# PCB-SSB-1x4.net
KiCad netlist of a schematic drawn in EAGLE
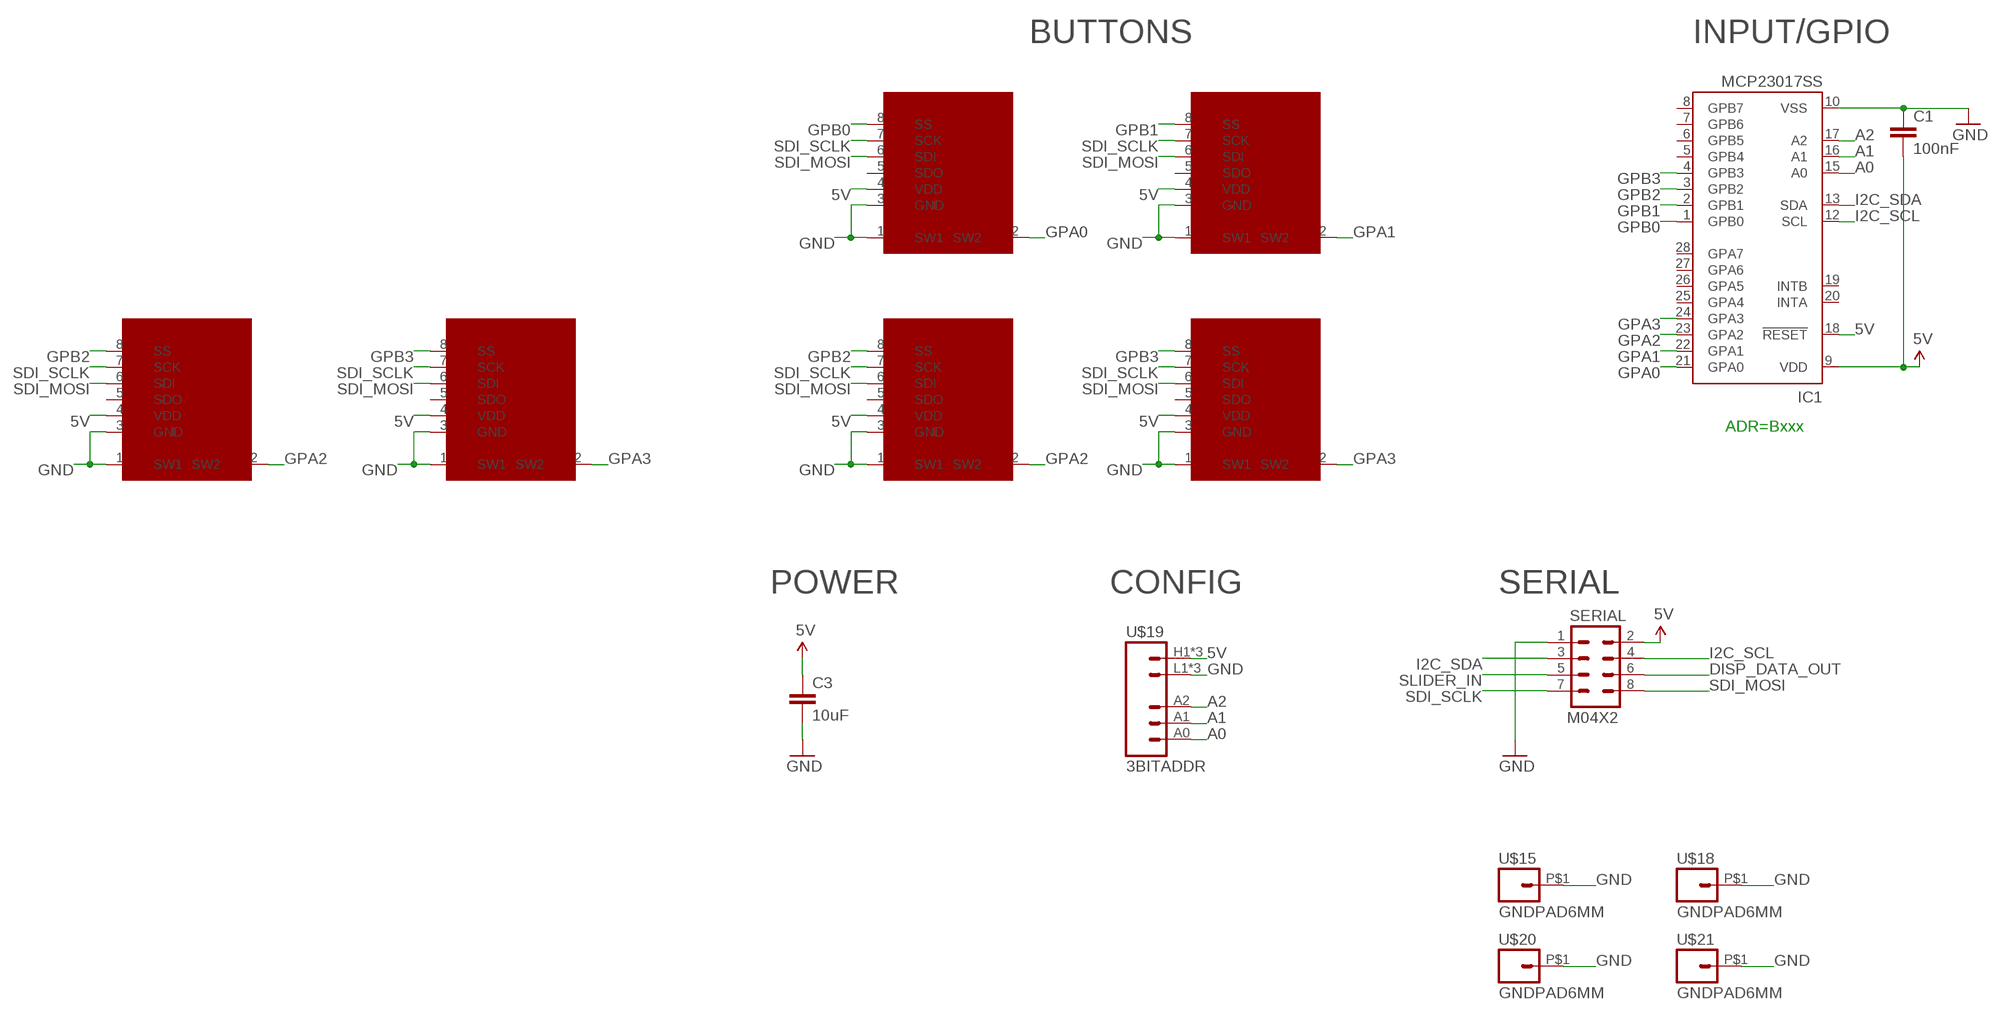
[diagram p0: schematic, sheet 1]

(export (version "E")
  (design (tool "Eeschema 10.0.6"))
  (components
    (comp (ref "C1")
      (value "100nF")
      (footprint "eagle-import:0603-CAP")
      (libsource (lib "eagle-import") (part "CAP0603-CAP"))
    )
    (comp (ref "C3")
      (value "10uF")
      (footprint "eagle-import:0805")
      (libsource (lib "eagle-import") (part "CAP0805"))
    )
    (comp (ref "IC1")
      (value "MCP23017SS")
      (footprint "eagle-import:SSOP28")
      (fields
        (field (name "MF") "MICROCHIP")
        (field (name "MPN") "MCP23017-E/SS")
        (field (name "MPN_1") "MCP23017-E/SS")
        (field (name "OC_FARNELL") "1467674")
        (field (name "OC_NEWARK") "31K2960")
      )
      (libsource (lib "eagle-import") (part "MCP23017SS"))
    )
    (comp (ref "SERIAL")
      (value "M04X2")
      (footprint "eagle-import:2X4")
      (libsource (lib "eagle-import") (part "M04X2"))
    )
    (comp (ref "SSW1")
      (value "SMART_SWITCHSMART_SWITCH_8PIN")
      (footprint "eagle-import:SMART_SWITCH")
      (libsource (lib "eagle-import") (part "SMART_SWITCHSMART_SWITCH_8PIN"))
    )
    (comp (ref "SSW2")
      (value "SMART_SWITCHSMART_SWITCH_8PIN")
      (footprint "eagle-import:SMART_SWITCH")
      (libsource (lib "eagle-import") (part "SMART_SWITCHSMART_SWITCH_8PIN"))
    )
    (comp (ref "SSW3")
      (value "SMART_SWITCHSMART_SWITCH_8PIN")
      (footprint "eagle-import:SMART_SWITCH")
      (libsource (lib "eagle-import") (part "SMART_SWITCHSMART_SWITCH_8PIN"))
    )
    (comp (ref "SSW3ALT")
      (value "SMART_SWITCHSMART_SWITCH_8PIN")
      (footprint "eagle-import:SMART_SWITCH")
      (libsource (lib "eagle-import") (part "SMART_SWITCHSMART_SWITCH_8PIN"))
    )
    (comp (ref "SSW4")
      (value "SMART_SWITCHSMART_SWITCH_8PIN")
      (footprint "eagle-import:SMART_SWITCH")
      (libsource (lib "eagle-import") (part "SMART_SWITCHSMART_SWITCH_8PIN"))
    )
    (comp (ref "SSW4ALT")
      (value "SMART_SWITCHSMART_SWITCH_8PIN")
      (footprint "eagle-import:SMART_SWITCH")
      (libsource (lib "eagle-import") (part "SMART_SWITCHSMART_SWITCH_8PIN"))
    )
    (comp (ref "U$15")
      (value "GNDPAD6MM")
      (footprint "eagle-import:3.2MMPAD6MM")
      (libsource (lib "eagle-import") (part "GNDPAD6MM"))
    )
    (comp (ref "U$18")
      (value "GNDPAD6MM")
      (footprint "eagle-import:3.2MMPAD6MM")
      (libsource (lib "eagle-import") (part "GNDPAD6MM"))
    )
    (comp (ref "U$19")
      (value "3BITADDR")
      (footprint "eagle-import:3BITADDR")
      (libsource (lib "eagle-import") (part "3BITADDR"))
    )
    (comp (ref "U$20")
      (value "GNDPAD6MM")
      (footprint "eagle-import:3.2MMPAD6MM")
      (libsource (lib "eagle-import") (part "GNDPAD6MM"))
    )
    (comp (ref "U$21")
      (value "GNDPAD6MM")
      (footprint "eagle-import:3.2MMPAD6MM")
      (libsource (lib "eagle-import") (part "GNDPAD6MM"))
    )
  )
  (nets
    (net (code "1") (name "/A0") (class "Default")
      (node (ref "IC1") (pin "15") (pinfunction "A0_15") (pintype "input"))
      (node (ref "U$19") (pin "A0") (pinfunction "A0_A0") (pintype "passive"))
    )
    (net (code "2") (name "/A1") (class "Default")
      (node (ref "IC1") (pin "16") (pinfunction "A1_16") (pintype "input"))
      (node (ref "U$19") (pin "A1") (pinfunction "A1_A1") (pintype "passive"))
    )
    (net (code "3") (name "/A2") (class "Default")
      (node (ref "IC1") (pin "17") (pinfunction "A2_17") (pintype "input"))
      (node (ref "U$19") (pin "A2") (pinfunction "A2_A2") (pintype "passive"))
    )
    (net (code "4") (name "/DISP_DATA_OUT") (class "Default")
      (node (ref "SERIAL") (pin "6") (pinfunction "6_6") (pintype "passive"))
    )
    (net (code "5") (name "/GPA0") (class "Default")
      (node (ref "IC1") (pin "21") (pinfunction "GPA0_21") (pintype "bidirectional"))
      (node (ref "SSW1") (pin "2") (pinfunction "SW2_2") (pintype "bidirectional"))
    )
    (net (code "6") (name "/GPA1") (class "Default")
      (node (ref "IC1") (pin "22") (pinfunction "GPA1_22") (pintype "bidirectional"))
      (node (ref "SSW2") (pin "2") (pinfunction "SW2_2") (pintype "bidirectional"))
    )
    (net (code "7") (name "/GPA2") (class "Default")
      (node (ref "IC1") (pin "23") (pinfunction "GPA2_23") (pintype "bidirectional"))
      (node (ref "SSW3") (pin "2") (pinfunction "SW2_2") (pintype "bidirectional"))
      (node (ref "SSW3ALT") (pin "2") (pinfunction "SW2_2") (pintype "bidirectional"))
    )
    (net (code "8") (name "/GPA3") (class "Default")
      (node (ref "IC1") (pin "24") (pinfunction "GPA3_24") (pintype "bidirectional"))
      (node (ref "SSW4") (pin "2") (pinfunction "SW2_2") (pintype "bidirectional"))
      (node (ref "SSW4ALT") (pin "2") (pinfunction "SW2_2") (pintype "bidirectional"))
    )
    (net (code "9") (name "/GPB0") (class "Default")
      (node (ref "IC1") (pin "1") (pinfunction "GPB0_1") (pintype "bidirectional"))
      (node (ref "SSW1") (pin "8") (pinfunction "SS_8") (pintype "bidirectional"))
    )
    (net (code "10") (name "/GPB1") (class "Default")
      (node (ref "IC1") (pin "2") (pinfunction "GPB1_2") (pintype "bidirectional"))
      (node (ref "SSW2") (pin "8") (pinfunction "SS_8") (pintype "bidirectional"))
    )
    (net (code "11") (name "/GPB2") (class "Default")
      (node (ref "IC1") (pin "3") (pinfunction "GPB2_3") (pintype "bidirectional"))
      (node (ref "SSW3") (pin "8") (pinfunction "SS_8") (pintype "bidirectional"))
      (node (ref "SSW3ALT") (pin "8") (pinfunction "SS_8") (pintype "bidirectional"))
    )
    (net (code "12") (name "/GPB3") (class "Default")
      (node (ref "IC1") (pin "4") (pinfunction "GPB3_4") (pintype "bidirectional"))
      (node (ref "SSW4") (pin "8") (pinfunction "SS_8") (pintype "bidirectional"))
      (node (ref "SSW4ALT") (pin "8") (pinfunction "SS_8") (pintype "bidirectional"))
    )
    (net (code "13") (name "/I2C_SCL") (class "Default")
      (node (ref "IC1") (pin "12") (pinfunction "SCL_12") (pintype "input"))
      (node (ref "SERIAL") (pin "4") (pinfunction "4_4") (pintype "passive"))
    )
    (net (code "14") (name "/I2C_SDA") (class "Default")
      (node (ref "IC1") (pin "13") (pinfunction "SDA_13") (pintype "bidirectional"))
      (node (ref "SERIAL") (pin "3") (pinfunction "3_3") (pintype "passive"))
    )
    (net (code "15") (name "/SDI_MOSI") (class "Default")
      (node (ref "SERIAL") (pin "8") (pinfunction "8_8") (pintype "passive"))
      (node (ref "SSW1") (pin "6") (pinfunction "SDI_6") (pintype "bidirectional"))
      (node (ref "SSW2") (pin "6") (pinfunction "SDI_6") (pintype "bidirectional"))
      (node (ref "SSW3") (pin "6") (pinfunction "SDI_6") (pintype "bidirectional"))
      (node (ref "SSW3ALT") (pin "6") (pinfunction "SDI_6") (pintype "bidirectional"))
      (node (ref "SSW4") (pin "6") (pinfunction "SDI_6") (pintype "bidirectional"))
      (node (ref "SSW4ALT") (pin "6") (pinfunction "SDI_6") (pintype "bidirectional"))
    )
    (net (code "16") (name "/SDI_SCLK") (class "Default")
      (node (ref "SERIAL") (pin "7") (pinfunction "7_7") (pintype "passive"))
      (node (ref "SSW1") (pin "7") (pinfunction "SCK_7") (pintype "bidirectional"))
      (node (ref "SSW2") (pin "7") (pinfunction "SCK_7") (pintype "bidirectional"))
      (node (ref "SSW3") (pin "7") (pinfunction "SCK_7") (pintype "bidirectional"))
      (node (ref "SSW3ALT") (pin "7") (pinfunction "SCK_7") (pintype "bidirectional"))
      (node (ref "SSW4") (pin "7") (pinfunction "SCK_7") (pintype "bidirectional"))
      (node (ref "SSW4ALT") (pin "7") (pinfunction "SCK_7") (pintype "bidirectional"))
    )
    (net (code "17") (name "/SLIDER_IN") (class "Default")
      (node (ref "SERIAL") (pin "5") (pinfunction "5_5") (pintype "passive"))
    )
    (net (code "18") (name "5V") (class "Default")
      (node (ref "C1") (pin "2") (pinfunction "2_2") (pintype "passive"))
      (node (ref "C3") (pin "1") (pinfunction "1_1") (pintype "passive"))
      (node (ref "IC1") (pin "18") (pinfunction "~{RESET}_18") (pintype "input"))
      (node (ref "IC1") (pin "9") (pinfunction "VDD_9") (pintype "power_in"))
      (node (ref "SERIAL") (pin "2") (pinfunction "2_2") (pintype "passive"))
      (node (ref "SSW1") (pin "4") (pinfunction "VDD_4") (pintype "bidirectional"))
      (node (ref "SSW2") (pin "4") (pinfunction "VDD_4") (pintype "bidirectional"))
      (node (ref "SSW3") (pin "4") (pinfunction "VDD_4") (pintype "bidirectional"))
      (node (ref "SSW3ALT") (pin "4") (pinfunction "VDD_4") (pintype "bidirectional"))
      (node (ref "SSW4") (pin "4") (pinfunction "VDD_4") (pintype "bidirectional"))
      (node (ref "SSW4ALT") (pin "4") (pinfunction "VDD_4") (pintype "bidirectional"))
      (node (ref "U$19") (pin "H1") (pinfunction "VCC_H1") (pintype "passive"))
      (node (ref "U$19") (pin "H2") (pinfunction "VCC_H2") (pintype "passive"))
      (node (ref "U$19") (pin "H3") (pinfunction "VCC_H3") (pintype "passive"))
    )
    (net (code "19") (name "GND") (class "Default")
      (node (ref "C1") (pin "1") (pinfunction "1_1") (pintype "passive"))
      (node (ref "C3") (pin "2") (pinfunction "2_2") (pintype "passive"))
      (node (ref "IC1") (pin "10") (pinfunction "VSS_10") (pintype "power_in"))
      (node (ref "SERIAL") (pin "1") (pinfunction "1_1") (pintype "passive"))
      (node (ref "SSW1") (pin "1") (pinfunction "SW1_1") (pintype "bidirectional"))
      (node (ref "SSW1") (pin "3") (pinfunction "GND_3") (pintype "bidirectional"))
      (node (ref "SSW2") (pin "1") (pinfunction "SW1_1") (pintype "bidirectional"))
      (node (ref "SSW2") (pin "3") (pinfunction "GND_3") (pintype "bidirectional"))
      (node (ref "SSW3") (pin "1") (pinfunction "SW1_1") (pintype "bidirectional"))
      (node (ref "SSW3") (pin "3") (pinfunction "GND_3") (pintype "bidirectional"))
      (node (ref "SSW3ALT") (pin "1") (pinfunction "SW1_1") (pintype "bidirectional"))
      (node (ref "SSW3ALT") (pin "3") (pinfunction "GND_3") (pintype "bidirectional"))
      (node (ref "SSW4") (pin "1") (pinfunction "SW1_1") (pintype "bidirectional"))
      (node (ref "SSW4") (pin "3") (pinfunction "GND_3") (pintype "bidirectional"))
      (node (ref "SSW4ALT") (pin "1") (pinfunction "SW1_1") (pintype "bidirectional"))
      (node (ref "SSW4ALT") (pin "3") (pinfunction "GND_3") (pintype "bidirectional"))
      (node (ref "U$15") (pin "P$1") (pinfunction "1_P$1") (pintype "passive"))
      (node (ref "U$18") (pin "P$1") (pinfunction "1_P$1") (pintype "passive"))
      (node (ref "U$19") (pin "L1") (pinfunction "GND_L1") (pintype "passive"))
      (node (ref "U$19") (pin "L2") (pinfunction "GND_L2") (pintype "passive"))
      (node (ref "U$19") (pin "L3") (pinfunction "GND_L3") (pintype "passive"))
      (node (ref "U$20") (pin "P$1") (pinfunction "1_P$1") (pintype "passive"))
      (node (ref "U$21") (pin "P$1") (pinfunction "1_P$1") (pintype "passive"))
    )
    (net (code "20") (name "unconnected-(IC1-GPA4-Pad25)") (class "Default")
      (node (ref "IC1") (pin "25") (pinfunction "GPA4_25") (pintype "bidirectional"))
    )
    (net (code "21") (name "unconnected-(IC1-GPA5-Pad26)") (class "Default")
      (node (ref "IC1") (pin "26") (pinfunction "GPA5_26") (pintype "bidirectional"))
    )
    (net (code "22") (name "unconnected-(IC1-GPA6-Pad27)") (class "Default")
      (node (ref "IC1") (pin "27") (pinfunction "GPA6_27") (pintype "bidirectional"))
    )
    (net (code "23") (name "unconnected-(IC1-GPA7-Pad28)") (class "Default")
      (node (ref "IC1") (pin "28") (pinfunction "GPA7_28") (pintype "bidirectional"))
    )
    (net (code "24") (name "unconnected-(IC1-GPB4-Pad5)") (class "Default")
      (node (ref "IC1") (pin "5") (pinfunction "GPB4_5") (pintype "bidirectional"))
    )
    (net (code "25") (name "unconnected-(IC1-GPB5-Pad6)") (class "Default")
      (node (ref "IC1") (pin "6") (pinfunction "GPB5_6") (pintype "bidirectional"))
    )
    (net (code "26") (name "unconnected-(IC1-GPB6-Pad7)") (class "Default")
      (node (ref "IC1") (pin "7") (pinfunction "GPB6_7") (pintype "bidirectional"))
    )
    (net (code "27") (name "unconnected-(IC1-GPB7-Pad8)") (class "Default")
      (node (ref "IC1") (pin "8") (pinfunction "GPB7_8") (pintype "bidirectional"))
    )
    (net (code "28") (name "unconnected-(IC1-INTA-Pad20)") (class "Default")
      (node (ref "IC1") (pin "20") (pinfunction "INTA_20") (pintype "output"))
    )
    (net (code "29") (name "unconnected-(IC1-INTB-Pad19)") (class "Default")
      (node (ref "IC1") (pin "19") (pinfunction "INTB_19") (pintype "output"))
    )
    (net (code "30") (name "unconnected-(SSW1-SDO-Pad5)") (class "Default")
      (node (ref "SSW1") (pin "5") (pinfunction "SDO_5") (pintype "bidirectional"))
    )
    (net (code "31") (name "unconnected-(SSW2-SDO-Pad5)") (class "Default")
      (node (ref "SSW2") (pin "5") (pinfunction "SDO_5") (pintype "bidirectional"))
    )
    (net (code "32") (name "unconnected-(SSW3-SDO-Pad5)") (class "Default")
      (node (ref "SSW3") (pin "5") (pinfunction "SDO_5") (pintype "bidirectional"))
    )
    (net (code "33") (name "unconnected-(SSW3ALT-SDO-Pad5)") (class "Default")
      (node (ref "SSW3ALT") (pin "5") (pinfunction "SDO_5") (pintype "bidirectional"))
    )
    (net (code "34") (name "unconnected-(SSW4-SDO-Pad5)") (class "Default")
      (node (ref "SSW4") (pin "5") (pinfunction "SDO_5") (pintype "bidirectional"))
    )
    (net (code "35") (name "unconnected-(SSW4ALT-SDO-Pad5)") (class "Default")
      (node (ref "SSW4ALT") (pin "5") (pinfunction "SDO_5") (pintype "bidirectional"))
    )
  )
)
